# SERIAL_FMU_REV_2A.net
KiCad netlist of a schematic drawn in Altium Designer
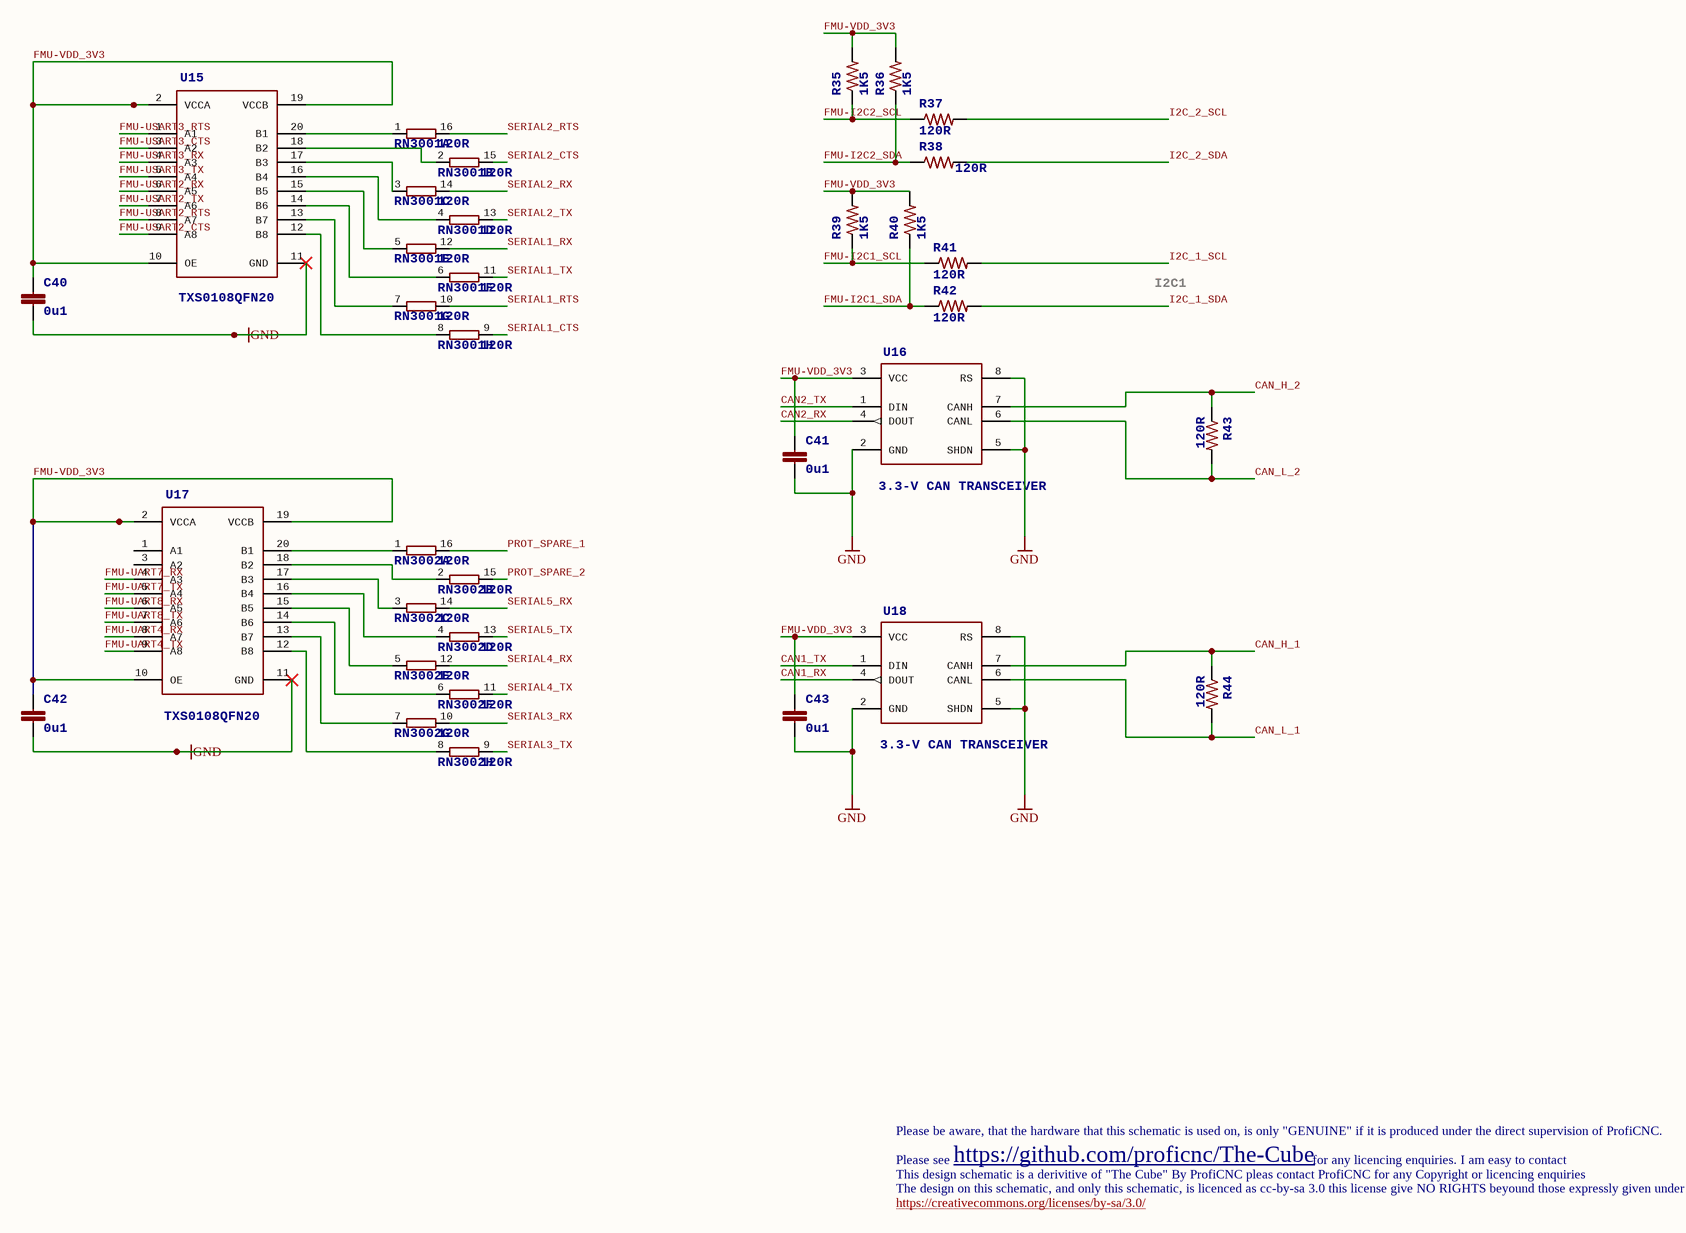
[diagram p0: SERIAL_FMU_REV_2A.SchDoc]

(export (version "E")
  (design (tool "Eeschema 10.0.6"))
  (components
    (comp (ref "C40")
      (value "0u1")
      (footprint "0402-CAP")
      (description "CAP CER 0.1UF 16V Y5V 0402")
      (libsource (lib "pixhawk2") (part "CAP0402"))
    )
    (comp (ref "C41")
      (value "0u1")
      (footprint "0402-CAP")
      (description "CAP CER 0.1UF 16V Y5V 0402")
      (libsource (lib "pixhawk2") (part "CAP0402"))
    )
    (comp (ref "C42")
      (value "0u1")
      (footprint "0402-CAP")
      (description "CAP CER 0.1UF 16V Y5V 0402")
      (libsource (lib "pixhawk2") (part "CAP0402"))
    )
    (comp (ref "C43")
      (value "0u1")
      (footprint "0402-CAP")
      (description "CAP CER 0.1UF 16V Y5V 0402")
      (libsource (lib "pixhawk2") (part "CAP0402"))
    )
    (comp (ref "R35")
      (value "1K5")
      (footprint "0402-RES")
      (description "RES 1.5K OHM 1/16W 1% 0402 SMD")
      (libsource (lib "pixhawk2") (part "RESISTOR0402-RES"))
    )
    (comp (ref "R36")
      (value "1K5")
      (footprint "0402-RES")
      (description "RES 1.5K OHM 1/16W 1% 0402 SMD")
      (libsource (lib "pixhawk2") (part "RESISTOR0402-RES"))
    )
    (comp (ref "R37")
      (value "120R")
      (footprint "0402-RES")
      (description "RES 120 OHM 1/16W 1% 0402 SMD")
      (libsource (lib "pixhawk2") (part "RESISTOR0402-RES"))
    )
    (comp (ref "R38")
      (value "120R")
      (footprint "0402-RES")
      (description "RES 120 OHM 1/16W 1% 0402 SMD")
      (libsource (lib "pixhawk2") (part "RESISTOR0402-RES"))
    )
    (comp (ref "R39")
      (value "1K5")
      (footprint "0402-RES")
      (description "RES 1.5K OHM 1/16W 1% 0402 SMD")
      (libsource (lib "pixhawk2") (part "RESISTOR0402-RES"))
    )
    (comp (ref "R40")
      (value "1K5")
      (footprint "0402-RES")
      (description "RES 1.5K OHM 1/16W 1% 0402 SMD")
      (libsource (lib "pixhawk2") (part "RESISTOR0402-RES"))
    )
    (comp (ref "R41")
      (value "120R")
      (footprint "0402-RES")
      (description "RES 120 OHM 1/16W 1% 0402 SMD")
      (libsource (lib "pixhawk2") (part "RESISTOR0402-RES"))
    )
    (comp (ref "R42")
      (value "120R")
      (footprint "0402-RES")
      (description "RES 120 OHM 1/16W 1% 0402 SMD")
      (libsource (lib "pixhawk2") (part "RESISTOR0402-RES"))
    )
    (comp (ref "R43")
      (value "120R")
      (footprint "0402-RES")
      (description "RES 120 OHM 1/16W 1% 0402 SMD")
      (libsource (lib "pixhawk2") (part "RESISTOR0402-RES"))
    )
    (comp (ref "R44")
      (value "120R")
      (footprint "0402-RES")
      (description "RES 120 OHM 1/16W 1% 0402 SMD")
      (libsource (lib "pixhawk2") (part "RESISTOR0402-RES"))
    )
    (comp (ref "RN3001")
      (value "120R")
      (footprint "EXB2HV")
      (description "RES ARRAY 120 OHM 8 RES 1506")
      (libsource (lib "pixhawk2") (part "8R-NEXB2HV-120R"))
    )
    (comp (ref "RN3002")
      (value "120R")
      (footprint "EXB2HV")
      (description "RES ARRAY 120 OHM 8 RES 1506")
      (libsource (lib "pixhawk2") (part "8R-NEXB2HV-120R"))
    )
    (comp (ref "U15")
      (value "TXS0108QFN20")
      (footprint "QFN20-RGY")
      (description "IC XLATR VOLT-LVL 8B BDIR 20QFN")
      (libsource (lib "pixhawk2") (part "TXS0108QFN20"))
    )
    (comp (ref "U16")
      (value "3.3-V CAN TRANSCEIVER")
      (footprint "SOT23-8")
      (description "IC TXRX CAN 1MBPS SOT23-8")
      (libsource (lib "pixhawk2") (part "MAX3051MAX3051EKA"))
    )
    (comp (ref "U17")
      (value "TXS0108QFN20")
      (footprint "QFN20-RGY")
      (description "IC XLATR VOLT-LVL 8B BDIR 20QFN")
      (libsource (lib "pixhawk2") (part "TXS0108QFN20"))
    )
    (comp (ref "U18")
      (value "3.3-V CAN TRANSCEIVER")
      (footprint "SOT23-8")
      (description "IC TXRX CAN 1MBPS SOT23-8")
      (libsource (lib "pixhawk2") (part "MAX3051MAX3051EKA"))
    )
  )
  (nets
    (net (code "1") (name "/CAN1_RX") (class "Default")
      (node (ref "U18") (pin "4") (pinfunction "DOUT_4") (pintype "output"))
    )
    (net (code "2") (name "/CAN1_TX") (class "Default")
      (node (ref "U18") (pin "1") (pinfunction "DIN_1") (pintype "passive"))
    )
    (net (code "3") (name "/CAN2_RX") (class "Default")
      (node (ref "U16") (pin "4") (pinfunction "DOUT_4") (pintype "output"))
    )
    (net (code "4") (name "/CAN2_TX") (class "Default")
      (node (ref "U16") (pin "1") (pinfunction "DIN_1") (pintype "passive"))
    )
    (net (code "5") (name "/CAN_H_1") (class "Default")
      (node (ref "R44") (pin "P$1") (pinfunction "1_P$1") (pintype "passive"))
      (node (ref "U18") (pin "7") (pinfunction "CANH_7") (pintype "passive"))
    )
    (net (code "6") (name "/CAN_H_2") (class "Default")
      (node (ref "R43") (pin "P$1") (pinfunction "1_P$1") (pintype "passive"))
      (node (ref "U16") (pin "7") (pinfunction "CANH_7") (pintype "passive"))
    )
    (net (code "7") (name "/CAN_L_1") (class "Default")
      (node (ref "R44") (pin "P$2") (pinfunction "2_P$2") (pintype "passive"))
      (node (ref "U18") (pin "6") (pinfunction "CANL_6") (pintype "passive"))
    )
    (net (code "8") (name "/CAN_L_2") (class "Default")
      (node (ref "R43") (pin "P$2") (pinfunction "2_P$2") (pintype "passive"))
      (node (ref "U16") (pin "6") (pinfunction "CANL_6") (pintype "passive"))
    )
    (net (code "9") (name "/FMU-I2C1_SCL") (class "Default")
      (node (ref "R39") (pin "P$1") (pinfunction "1_P$1") (pintype "passive"))
      (node (ref "R41") (pin "P$1") (pinfunction "1_P$1") (pintype "passive"))
    )
    (net (code "10") (name "/FMU-I2C1_SDA") (class "Default")
      (node (ref "R40") (pin "P$1") (pinfunction "1_P$1") (pintype "passive"))
      (node (ref "R42") (pin "P$1") (pinfunction "1_P$1") (pintype "passive"))
    )
    (net (code "11") (name "/FMU-I2C2_SCL") (class "Default")
      (node (ref "R35") (pin "P$1") (pinfunction "1_P$1") (pintype "passive"))
      (node (ref "R37") (pin "P$1") (pinfunction "1_P$1") (pintype "passive"))
    )
    (net (code "12") (name "/FMU-I2C2_SDA") (class "Default")
      (node (ref "R36") (pin "P$1") (pinfunction "1_P$1") (pintype "passive"))
      (node (ref "R38") (pin "P$1") (pinfunction "1_P$1") (pintype "passive"))
    )
    (net (code "13") (name "/FMU-UART4_RX") (class "Default")
      (node (ref "U17") (pin "8") (pinfunction "A7_8") (pintype "passive"))
    )
    (net (code "14") (name "/FMU-UART4_TX") (class "Default")
      (node (ref "U17") (pin "9") (pinfunction "A8_9") (pintype "passive"))
    )
    (net (code "15") (name "/FMU-UART7_RX") (class "Default")
      (node (ref "U17") (pin "4") (pinfunction "A3_4") (pintype "passive"))
    )
    (net (code "16") (name "/FMU-UART7_TX") (class "Default")
      (node (ref "U17") (pin "5") (pinfunction "A4_5") (pintype "passive"))
    )
    (net (code "17") (name "/FMU-UART8_RX") (class "Default")
      (node (ref "U17") (pin "6") (pinfunction "A5_6") (pintype "passive"))
    )
    (net (code "18") (name "/FMU-UART8_TX") (class "Default")
      (node (ref "U17") (pin "7") (pinfunction "A6_7") (pintype "passive"))
    )
    (net (code "19") (name "/FMU-USART2_CTS") (class "Default")
      (node (ref "U15") (pin "9") (pinfunction "A8_9") (pintype "passive"))
    )
    (net (code "20") (name "/FMU-USART2_RTS") (class "Default")
      (node (ref "U15") (pin "8") (pinfunction "A7_8") (pintype "passive"))
    )
    (net (code "21") (name "/FMU-USART2_RX") (class "Default")
      (node (ref "U15") (pin "6") (pinfunction "A5_6") (pintype "passive"))
    )
    (net (code "22") (name "/FMU-USART2_TX") (class "Default")
      (node (ref "U15") (pin "7") (pinfunction "A6_7") (pintype "passive"))
    )
    (net (code "23") (name "/FMU-USART3_CTS") (class "Default")
      (node (ref "U15") (pin "3") (pinfunction "A2_3") (pintype "passive"))
    )
    (net (code "24") (name "/FMU-USART3_RTS") (class "Default")
      (node (ref "U15") (pin "1") (pinfunction "A1_1") (pintype "passive"))
    )
    (net (code "25") (name "/FMU-USART3_RX") (class "Default")
      (node (ref "U15") (pin "4") (pinfunction "A3_4") (pintype "passive"))
    )
    (net (code "26") (name "/FMU-USART3_TX") (class "Default")
      (node (ref "U15") (pin "5") (pinfunction "A4_5") (pintype "passive"))
    )
    (net (code "27") (name "/FMU-VDD_3V3") (class "Default")
      (node (ref "C40") (pin "P$1") (pinfunction "1_P$1") (pintype "passive"))
      (node (ref "C41") (pin "P$1") (pinfunction "1_P$1") (pintype "passive"))
      (node (ref "C42") (pin "P$1") (pinfunction "1_P$1") (pintype "passive"))
      (node (ref "C43") (pin "P$1") (pinfunction "1_P$1") (pintype "passive"))
      (node (ref "R35") (pin "P$2") (pinfunction "2_P$2") (pintype "passive"))
      (node (ref "R36") (pin "P$2") (pinfunction "2_P$2") (pintype "passive"))
      (node (ref "R39") (pin "P$2") (pinfunction "2_P$2") (pintype "passive"))
      (node (ref "R40") (pin "P$2") (pinfunction "2_P$2") (pintype "passive"))
      (node (ref "U15") (pin "10") (pinfunction "OE_10") (pintype "passive"))
      (node (ref "U15") (pin "19") (pinfunction "VCCB_19") (pintype "passive"))
      (node (ref "U15") (pin "2") (pinfunction "VCCA_2") (pintype "passive"))
      (node (ref "U16") (pin "3") (pinfunction "VCC_3") (pintype "passive"))
      (node (ref "U17") (pin "10") (pinfunction "OE_10") (pintype "passive"))
      (node (ref "U17") (pin "19") (pinfunction "VCCB_19") (pintype "passive"))
      (node (ref "U17") (pin "2") (pinfunction "VCCA_2") (pintype "passive"))
      (node (ref "U18") (pin "3") (pinfunction "VCC_3") (pintype "passive"))
    )
    (net (code "28") (name "/I2C_1_SCL") (class "Default")
      (node (ref "R41") (pin "P$2") (pinfunction "2_P$2") (pintype "passive"))
    )
    (net (code "29") (name "/I2C_1_SDA") (class "Default")
      (node (ref "R42") (pin "P$2") (pinfunction "2_P$2") (pintype "passive"))
    )
    (net (code "30") (name "/I2C_2_SCL") (class "Default")
      (node (ref "R37") (pin "P$2") (pinfunction "2_P$2") (pintype "passive"))
    )
    (net (code "31") (name "/I2C_2_SDA") (class "Default")
      (node (ref "R38") (pin "P$2") (pinfunction "2_P$2") (pintype "passive"))
    )
    (net (code "32") (name "/PROT_SPARE_1") (class "Default")
      (node (ref "RN3002") (pin "16") (pinfunction "2_16") (pintype "passive"))
    )
    (net (code "33") (name "/PROT_SPARE_2") (class "Default")
      (node (ref "RN3002") (pin "15") (pinfunction "2_15") (pintype "passive"))
    )
    (net (code "34") (name "/SERIAL1_CTS") (class "Default")
      (node (ref "RN3001") (pin "9") (pinfunction "2_9") (pintype "passive"))
    )
    (net (code "35") (name "/SERIAL1_RTS") (class "Default")
      (node (ref "RN3001") (pin "10") (pinfunction "2_10") (pintype "passive"))
    )
    (net (code "36") (name "/SERIAL1_RX") (class "Default")
      (node (ref "RN3001") (pin "12") (pinfunction "2_12") (pintype "passive"))
    )
    (net (code "37") (name "/SERIAL1_TX") (class "Default")
      (node (ref "RN3001") (pin "11") (pinfunction "2_11") (pintype "passive"))
    )
    (net (code "38") (name "/SERIAL2_CTS") (class "Default")
      (node (ref "RN3001") (pin "15") (pinfunction "2_15") (pintype "passive"))
    )
    (net (code "39") (name "/SERIAL2_RTS") (class "Default")
      (node (ref "RN3001") (pin "16") (pinfunction "2_16") (pintype "passive"))
    )
    (net (code "40") (name "/SERIAL2_RX") (class "Default")
      (node (ref "RN3001") (pin "14") (pinfunction "2_14") (pintype "passive"))
    )
    (net (code "41") (name "/SERIAL2_TX") (class "Default")
      (node (ref "RN3001") (pin "13") (pinfunction "2_13") (pintype "passive"))
    )
    (net (code "42") (name "/SERIAL3_RX") (class "Default")
      (node (ref "RN3002") (pin "10") (pinfunction "2_10") (pintype "passive"))
    )
    (net (code "43") (name "/SERIAL3_TX") (class "Default")
      (node (ref "RN3002") (pin "9") (pinfunction "2_9") (pintype "passive"))
    )
    (net (code "44") (name "/SERIAL4_RX") (class "Default")
      (node (ref "RN3002") (pin "12") (pinfunction "2_12") (pintype "passive"))
    )
    (net (code "45") (name "/SERIAL4_TX") (class "Default")
      (node (ref "RN3002") (pin "11") (pinfunction "2_11") (pintype "passive"))
    )
    (net (code "46") (name "/SERIAL5_RX") (class "Default")
      (node (ref "RN3002") (pin "14") (pinfunction "2_14") (pintype "passive"))
    )
    (net (code "47") (name "/SERIAL5_TX") (class "Default")
      (node (ref "RN3002") (pin "13") (pinfunction "2_13") (pintype "passive"))
    )
    (net (code "48") (name "GND") (class "Default")
      (node (ref "C40") (pin "P$2") (pinfunction "2_P$2") (pintype "passive"))
      (node (ref "C41") (pin "P$2") (pinfunction "2_P$2") (pintype "passive"))
      (node (ref "C42") (pin "P$2") (pinfunction "2_P$2") (pintype "passive"))
      (node (ref "C43") (pin "P$2") (pinfunction "2_P$2") (pintype "passive"))
      (node (ref "U15") (pin "11") (pinfunction "GND_11") (pintype "open_emitter"))
      (node (ref "U16") (pin "2") (pinfunction "GND_2") (pintype "open_emitter"))
      (node (ref "U16") (pin "5") (pinfunction "SHDN_5") (pintype "passive"))
      (node (ref "U16") (pin "8") (pinfunction "RS_8") (pintype "passive"))
      (node (ref "U17") (pin "11") (pinfunction "GND_11") (pintype "open_emitter"))
      (node (ref "U18") (pin "2") (pinfunction "GND_2") (pintype "open_emitter"))
      (node (ref "U18") (pin "5") (pinfunction "SHDN_5") (pintype "passive"))
      (node (ref "U18") (pin "8") (pinfunction "RS_8") (pintype "passive"))
    )
    (net (code "49") (name "Net-(RN3001B-1)") (class "Default")
      (node (ref "RN3001") (pin "2") (pinfunction "1_2") (pintype "passive"))
      (node (ref "U15") (pin "18") (pinfunction "B2_18") (pintype "passive"))
    )
    (net (code "50") (name "Net-(RN3001C-1)") (class "Default")
      (node (ref "RN3001") (pin "3") (pinfunction "1_3") (pintype "passive"))
      (node (ref "U15") (pin "17") (pinfunction "B3_17") (pintype "passive"))
    )
    (net (code "51") (name "Net-(RN3001D-1)") (class "Default")
      (node (ref "RN3001") (pin "4") (pinfunction "1_4") (pintype "passive"))
      (node (ref "U15") (pin "16") (pinfunction "B4_16") (pintype "passive"))
    )
    (net (code "52") (name "Net-(RN3001E-1)") (class "Default")
      (node (ref "RN3001") (pin "5") (pinfunction "1_5") (pintype "passive"))
      (node (ref "U15") (pin "15") (pinfunction "B5_15") (pintype "passive"))
    )
    (net (code "53") (name "Net-(RN3001F-1)") (class "Default")
      (node (ref "RN3001") (pin "6") (pinfunction "1_6") (pintype "passive"))
      (node (ref "U15") (pin "14") (pinfunction "B6_14") (pintype "passive"))
    )
    (net (code "54") (name "Net-(RN3001G-1)") (class "Default")
      (node (ref "RN3001") (pin "7") (pinfunction "1_7") (pintype "passive"))
      (node (ref "U15") (pin "13") (pinfunction "B7_13") (pintype "passive"))
    )
    (net (code "55") (name "Net-(RN3001H-1)") (class "Default")
      (node (ref "RN3001") (pin "8") (pinfunction "1_8") (pintype "passive"))
      (node (ref "U15") (pin "12") (pinfunction "B8_12") (pintype "passive"))
    )
    (net (code "56") (name "Net-(RN3002B-1)") (class "Default")
      (node (ref "RN3002") (pin "2") (pinfunction "1_2") (pintype "passive"))
      (node (ref "U17") (pin "18") (pinfunction "B2_18") (pintype "passive"))
    )
    (net (code "57") (name "Net-(RN3002C-1)") (class "Default")
      (node (ref "RN3002") (pin "3") (pinfunction "1_3") (pintype "passive"))
      (node (ref "U17") (pin "17") (pinfunction "B3_17") (pintype "passive"))
    )
    (net (code "58") (name "Net-(RN3002D-1)") (class "Default")
      (node (ref "RN3002") (pin "4") (pinfunction "1_4") (pintype "passive"))
      (node (ref "U17") (pin "16") (pinfunction "B4_16") (pintype "passive"))
    )
    (net (code "59") (name "Net-(RN3002E-1)") (class "Default")
      (node (ref "RN3002") (pin "5") (pinfunction "1_5") (pintype "passive"))
      (node (ref "U17") (pin "15") (pinfunction "B5_15") (pintype "passive"))
    )
    (net (code "60") (name "Net-(RN3002F-1)") (class "Default")
      (node (ref "RN3002") (pin "6") (pinfunction "1_6") (pintype "passive"))
      (node (ref "U17") (pin "14") (pinfunction "B6_14") (pintype "passive"))
    )
    (net (code "61") (name "Net-(RN3002G-1)") (class "Default")
      (node (ref "RN3002") (pin "7") (pinfunction "1_7") (pintype "passive"))
      (node (ref "U17") (pin "13") (pinfunction "B7_13") (pintype "passive"))
    )
    (net (code "62") (name "Net-(RN3002H-1)") (class "Default")
      (node (ref "RN3002") (pin "8") (pinfunction "1_8") (pintype "passive"))
      (node (ref "U17") (pin "12") (pinfunction "B8_12") (pintype "passive"))
    )
    (net (code "63") (name "Net-(U15-B1)") (class "Default")
      (node (ref "RN3001") (pin "1") (pinfunction "1_1") (pintype "passive"))
      (node (ref "U15") (pin "20") (pinfunction "B1_20") (pintype "passive"))
    )
    (net (code "64") (name "Net-(U17-B1)") (class "Default")
      (node (ref "RN3002") (pin "1") (pinfunction "1_1") (pintype "passive"))
      (node (ref "U17") (pin "20") (pinfunction "B1_20") (pintype "passive"))
    )
    (net (code "65") (name "unconnected-(U17-A1-Pad1)") (class "Default")
      (node (ref "U17") (pin "1") (pinfunction "A1_1") (pintype "passive"))
    )
    (net (code "66") (name "unconnected-(U17-A2-Pad3)") (class "Default")
      (node (ref "U17") (pin "3") (pinfunction "A2_3") (pintype "passive"))
    )
  )
)
